# Ethernet_Sheet.net
KiCad netlist of a schematic drawn in Altium Designer
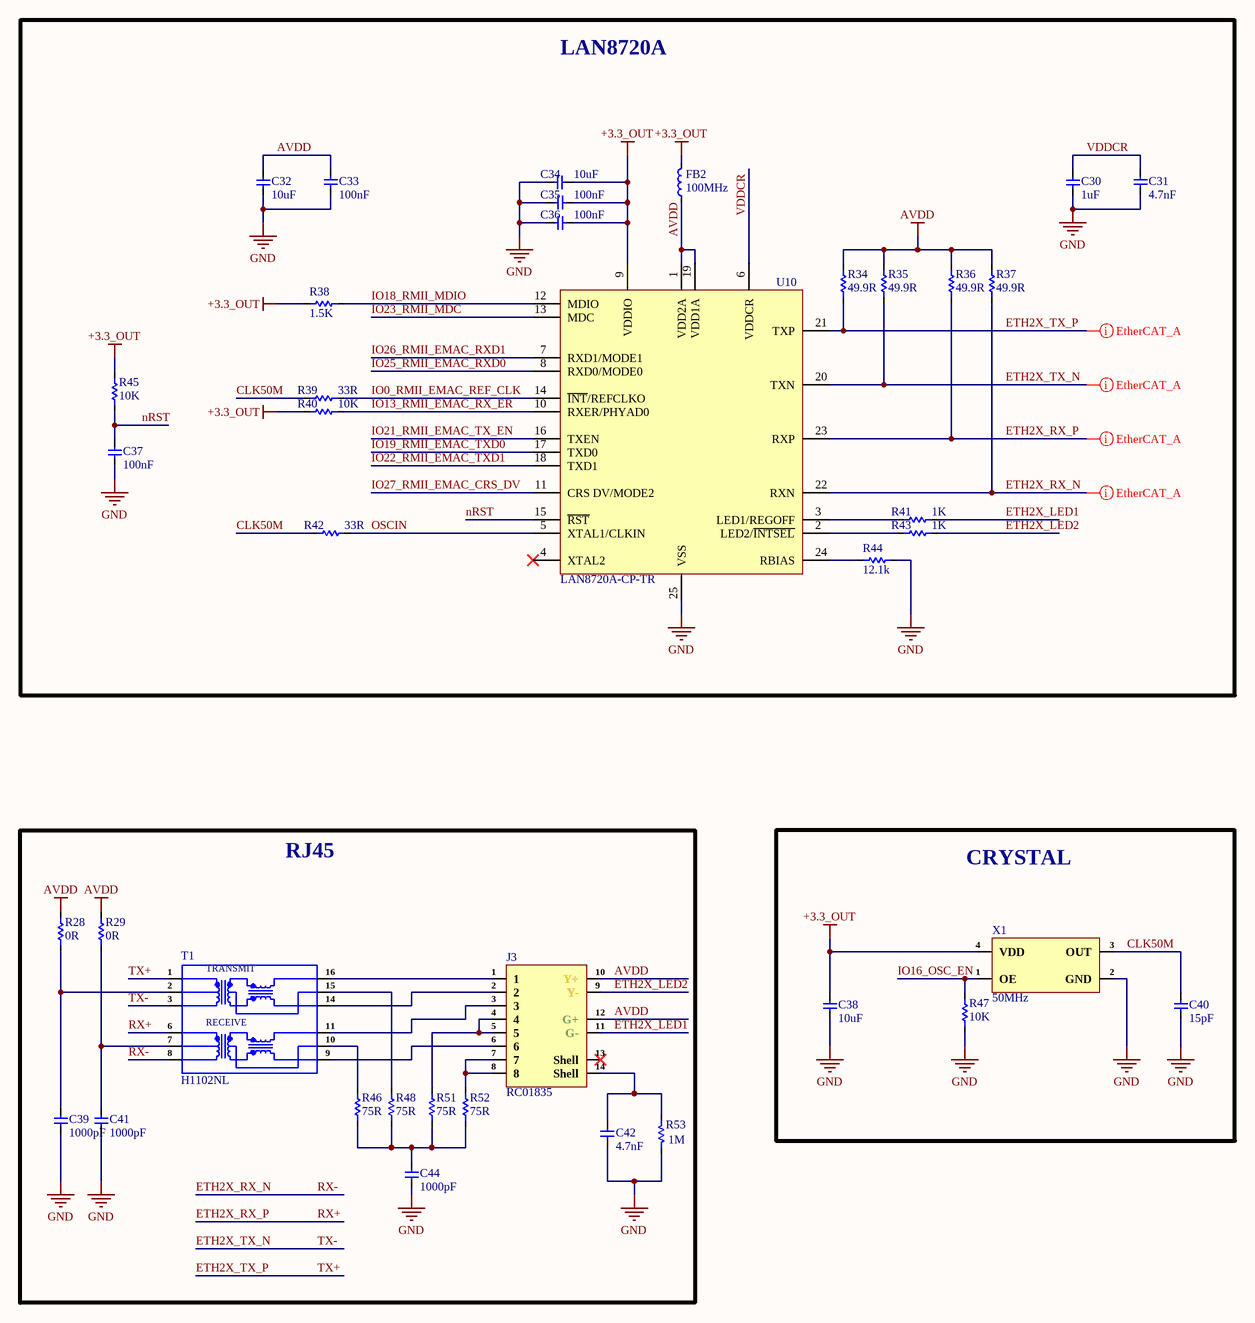
[diagram p0: Ethernet_Sheet.SchDoc]

(export (version "E")
  (design (tool "Eeschema 10.0.6"))
  (components
    (comp (ref "C30")
      (value "1uF")
      (footprint "Cap-0402")
      (description "CAP CER 1UF 16V X5R 0402")
      (fields
        (field (name "MANUFACTURER") "Yageo")
        (field (name "MANUFACTURER PART NUMBER") "CC0402KRX5R7BB105")
      )
      (libsource (lib "eSpark Libraries") (part "CC0402KRX5R7BB105"))
    )
    (comp (ref "C31")
      (value "4.7nF")
      (footprint "Cap-0402")
      (description "CAP CER 4700PF 50V X7R 0402")
      (fields
        (field (name "MANUFACTURER") "Yageo")
        (field (name "MANUFACTURER PART NUMBER") "CC0402KRX7R9BB472")
      )
      (libsource (lib "eSpark Libraries") (part "CC0402KRX7R9BB472"))
    )
    (comp (ref "C32")
      (value "10uF")
      (footprint "Cap-0603")
      (description "CAP CER 10UF 25V X5R 0603")
      (fields
        (field (name "MANUFACTURER") "Samsung")
        (field (name "MANUFACTURER PART NUMBER") "CL10A106MA8NRNC")
      )
      (libsource (lib "eSpark Libraries") (part "CL10A106MA8NRNC"))
    )
    (comp (ref "C33")
      (value "100nF")
      (footprint "cap-0402")
      (description "CAP CER 0.1UF 50V X7R 0402")
      (fields
        (field (name "MANUFACTURER") "TDK")
        (field (name "MANUFACTURER PART NUMBER") "C1005X7R1H104KT000F")
      )
      (libsource (lib "eSpark Libraries") (part "C1005X7R1H104KT000F"))
    )
    (comp (ref "C34")
      (value "10uF")
      (footprint "Cap-0603")
      (description "CAP CER 10UF 25V X5R 0603")
      (fields
        (field (name "MANUFACTURER") "Samsung")
        (field (name "MANUFACTURER PART NUMBER") "CL10A106MA8NRNC")
      )
      (libsource (lib "eSpark Libraries") (part "CL10A106MA8NRNC"))
    )
    (comp (ref "C35")
      (value "100nF")
      (footprint "cap-0402")
      (description "CAP CER 0.1UF 50V X7R 0402")
      (fields
        (field (name "MANUFACTURER") "TDK")
        (field (name "MANUFACTURER PART NUMBER") "C1005X7R1H104KT000F")
      )
      (libsource (lib "eSpark Libraries") (part "C1005X7R1H104KT000F"))
    )
    (comp (ref "C36")
      (value "100nF")
      (footprint "cap-0402")
      (description "CAP CER 0.1UF 50V X7R 0402")
      (fields
        (field (name "MANUFACTURER") "TDK")
        (field (name "MANUFACTURER PART NUMBER") "C1005X7R1H104KT000F")
      )
      (libsource (lib "eSpark Libraries") (part "C1005X7R1H104KT000F"))
    )
    (comp (ref "C37")
      (value "100nF")
      (footprint "cap-0402")
      (description "CAP CER 0.1UF 50V X7R 0402")
      (fields
        (field (name "MANUFACTURER") "TDK")
        (field (name "MANUFACTURER PART NUMBER") "C1005X7R1H104KT000F")
      )
      (libsource (lib "eSpark Libraries") (part "C1005X7R1H104KT000F"))
    )
    (comp (ref "C38")
      (value "10uF")
      (footprint "Cap-0603")
      (description "CAP CER 10UF 25V X5R 0603")
      (fields
        (field (name "MANUFACTURER") "Samsung")
        (field (name "MANUFACTURER PART NUMBER") "CL10A106MA8NRNC")
      )
      (libsource (lib "eSpark Libraries") (part "CL10A106MA8NRNC"))
    )
    (comp (ref "C39")
      (value "1000pF")
      (footprint "Cap-1206")
      (description "CAP CER 1000PF 2KV X7R 1206")
      (fields
        (field (name "MANUFACTURER") "Yageo")
        (field (name "MANUFACTURER PART NUMBER") "CC1206KKX7RDBB102")
      )
      (libsource (lib "eSpark Libraries") (part "CC1206KKX7RDBB102"))
    )
    (comp (ref "C40")
      (value "15pF")
      (footprint "Cap-0603")
      (description "CAP CER 15PF 50V C0G/NPO 0603")
      (fields
        (field (name "MANUFACTURER") "Yageo")
        (field (name "MANUFACTURER PART NUMBER") "CC0603JRNPO9BN150")
      )
      (libsource (lib "eSpark Libraries") (part "CC0603JRNPO9BN150"))
    )
    (comp (ref "C41")
      (value "1000pF")
      (footprint "Cap-1206")
      (description "CAP CER 1000PF 2KV X7R 1206")
      (fields
        (field (name "MANUFACTURER") "Yageo")
        (field (name "MANUFACTURER PART NUMBER") "CC1206KKX7RDBB102")
      )
      (libsource (lib "eSpark Libraries") (part "CC1206KKX7RDBB102"))
    )
    (comp (ref "C42")
      (value "4.7nF")
      (footprint "Cap-0402")
      (description "CAP CER 4700PF 50V X7R 0402")
      (fields
        (field (name "MANUFACTURER") "Yageo")
        (field (name "MANUFACTURER PART NUMBER") "CC0402KRX7R9BB472")
      )
      (libsource (lib "eSpark Libraries") (part "CC0402KRX7R9BB472"))
    )
    (comp (ref "C44")
      (value "1000pF")
      (footprint "Cap-1206")
      (description "CAP CER 1000PF 2KV X7R 1206")
      (fields
        (field (name "MANUFACTURER") "Yageo")
        (field (name "MANUFACTURER PART NUMBER") "CC1206KKX7RDBB102")
      )
      (libsource (lib "eSpark Libraries") (part "CC1206KKX7RDBB102"))
    )
    (comp (ref "FB2")
      (value "100MHz")
      (footprint "IND-1206")
      (description "FERRITE BEAD 120 OHM 1206 1LN")
      (fields
        (field (name "MANUFACTURER") "Murata")
        (field (name "MANUFACTURER PART NUMBER") "BLM31PG121SN1L")
      )
      (libsource (lib "eSpark Libraries") (part "BLM31PG121SN1L"))
    )
    (comp (ref "J3")
      (value "RC01835")
      (footprint "RC01835")
      (fields (field (name "MANUFACTURER") "RCH") (field (name "LCSC PART NUMBER") "C708648"))
      (libsource (lib "eSpark Libraries") (part "RC01835"))
    )
    (comp (ref "R28")
      (value "0R")
      (footprint "Res-0402")
      (description "RES 0 OHM JUMPER 1/16W 0402")
      (fields
        (field (name "MANUFACTURER") "Yageo")
        (field (name "MANUFACTURER PART NUMBER") "RC0402FR-070RL")
      )
      (libsource (lib "eSpark Libraries") (part "RC0402FR-070RL"))
    )
    (comp (ref "R29")
      (value "0R")
      (footprint "Res-0402")
      (description "RES 0 OHM JUMPER 1/16W 0402")
      (fields
        (field (name "MANUFACTURER") "Yageo")
        (field (name "MANUFACTURER PART NUMBER") "RC0402FR-070RL")
      )
      (libsource (lib "eSpark Libraries") (part "RC0402FR-070RL"))
    )
    (comp (ref "R34")
      (value "49.9R")
      (footprint "Res-0603")
      (description "RES 49.9 OHM 1% 1/10W 0603")
      (fields
        (field (name "MANUFACTURER") "Yageo")
        (field (name "MANUFACTURER PART NUMBER") "RC0603FR-0749R9L")
      )
      (libsource (lib "eSpark Libraries") (part "RC0603FR-0749R9L"))
    )
    (comp (ref "R35")
      (value "49.9R")
      (footprint "Res-0603")
      (description "RES 49.9 OHM 1% 1/10W 0603")
      (fields
        (field (name "MANUFACTURER") "Yageo")
        (field (name "MANUFACTURER PART NUMBER") "RC0603FR-0749R9L")
      )
      (libsource (lib "eSpark Libraries") (part "RC0603FR-0749R9L"))
    )
    (comp (ref "R36")
      (value "49.9R")
      (footprint "Res-0603")
      (description "RES 49.9 OHM 1% 1/10W 0603")
      (fields
        (field (name "MANUFACTURER") "Yageo")
        (field (name "MANUFACTURER PART NUMBER") "RC0603FR-0749R9L")
      )
      (libsource (lib "eSpark Libraries") (part "RC0603FR-0749R9L"))
    )
    (comp (ref "R37")
      (value "49.9R")
      (footprint "Res-0603")
      (description "RES 49.9 OHM 1% 1/10W 0603")
      (fields
        (field (name "MANUFACTURER") "Yageo")
        (field (name "MANUFACTURER PART NUMBER") "RC0603FR-0749R9L")
      )
      (libsource (lib "eSpark Libraries") (part "RC0603FR-0749R9L"))
    )
    (comp (ref "R38")
      (value "1.5K")
      (footprint "Res-0402")
      (description "RES 1.5K OHM 1% 1/16W 0402")
      (fields
        (field (name "MANUFACTURER") "Yageo")
        (field (name "MANUFACTURER PART NUMBER") "RC0402FR-071K5L")
      )
      (libsource (lib "eSpark Libraries") (part "RC0402FR-071K5L"))
    )
    (comp (ref "R39")
      (value "33R")
      (footprint "Res-0402")
      (description "RES 33 OHM 1% 1/16W 0402")
      (fields
        (field (name "MANUFACTURER") "Yageo")
        (field (name "MANUFACTURER PART NUMBER") "RC0402FR-0733RL")
      )
      (libsource (lib "eSpark Libraries") (part "RC0402FR-0733RL"))
    )
    (comp (ref "R40")
      (value "10K")
      (footprint "Res-0402")
      (description "RES 10K OHM 1% 1/16W 0402")
      (fields
        (field (name "MANUFACTURER") "Yageo")
        (field (name "MANUFACTURER PART NUMBER") "RC0402FR-0710KL")
      )
      (libsource (lib "eSpark Libraries") (part "RC0402FR-0710KL"))
    )
    (comp (ref "R41")
      (value "1K")
      (footprint "Res-0402")
      (description "RES SMD 1K OHM 1% 1/5W 0402")
      (fields
        (field (name "MANUFACTURER") "Vishay Dale")
        (field (name "MANUFACTURER PART NUMBER") "CRCW04021K00FKEDHP")
      )
      (libsource (lib "eSpark Libraries") (part "CRCW04021K00FKEDHP"))
    )
    (comp (ref "R42")
      (value "33R")
      (footprint "Res-0402")
      (description "RES 33 OHM 1% 1/16W 0402")
      (fields
        (field (name "MANUFACTURER") "Yageo")
        (field (name "MANUFACTURER PART NUMBER") "RC0402FR-0733RL")
      )
      (libsource (lib "eSpark Libraries") (part "RC0402FR-0733RL"))
    )
    (comp (ref "R43")
      (value "1K")
      (footprint "Res-0402")
      (description "RES SMD 1K OHM 1% 1/5W 0402")
      (fields
        (field (name "MANUFACTURER") "Vishay Dale")
        (field (name "MANUFACTURER PART NUMBER") "CRCW04021K00FKEDHP")
      )
      (libsource (lib "eSpark Libraries") (part "CRCW04021K00FKEDHP"))
    )
    (comp (ref "R44")
      (value "12.1k")
      (footprint "Res-0402")
      (description "RES SMD 12.1KOHM 0.1% 1/16W 0402")
      (fields
        (field (name "MANUFACTURER") "Yageo")
        (field (name "MANUFACTURER PART NUMBER") "RT0402BRD0712K1L")
      )
      (libsource (lib "eSpark Libraries") (part "RT0402BRD0712K1L"))
    )
    (comp (ref "R45")
      (value "10K")
      (footprint "Res-0402")
      (description "RES 10K OHM 1% 1/16W 0402")
      (fields
        (field (name "MANUFACTURER") "Yageo")
        (field (name "MANUFACTURER PART NUMBER") "RC0402FR-0710KL")
      )
      (libsource (lib "eSpark Libraries") (part "RC0402FR-0710KL"))
    )
    (comp (ref "R46")
      (value "75R")
      (footprint "Res-0402")
      (description "RES 75 OHM 5% 1/16W 0402")
      (fields
        (field (name "MANUFACTURER") "Yageo")
        (field (name "MANUFACTURER PART NUMBER") "RC0402JR-0775RL")
      )
      (libsource (lib "eSpark Libraries") (part "RC0402JR-0775RL"))
    )
    (comp (ref "R47")
      (value "10K")
      (footprint "Res-0402")
      (description "RES 10K OHM 1% 1/16W 0402")
      (fields
        (field (name "MANUFACTURER") "Yageo")
        (field (name "MANUFACTURER PART NUMBER") "RC0402FR-0710KL")
      )
      (libsource (lib "eSpark Libraries") (part "RC0402FR-0710KL"))
    )
    (comp (ref "R48")
      (value "75R")
      (footprint "Res-0402")
      (description "RES 75 OHM 5% 1/16W 0402")
      (fields
        (field (name "MANUFACTURER") "Yageo")
        (field (name "MANUFACTURER PART NUMBER") "RC0402JR-0775RL")
      )
      (libsource (lib "eSpark Libraries") (part "RC0402JR-0775RL"))
    )
    (comp (ref "R51")
      (value "75R")
      (footprint "Res-0402")
      (description "RES 75 OHM 5% 1/16W 0402")
      (fields
        (field (name "MANUFACTURER") "Yageo")
        (field (name "MANUFACTURER PART NUMBER") "RC0402JR-0775RL")
      )
      (libsource (lib "eSpark Libraries") (part "RC0402JR-0775RL"))
    )
    (comp (ref "R52")
      (value "75R")
      (footprint "Res-0402")
      (description "RES 75 OHM 5% 1/16W 0402")
      (fields
        (field (name "MANUFACTURER") "Yageo")
        (field (name "MANUFACTURER PART NUMBER") "RC0402JR-0775RL")
      )
      (libsource (lib "eSpark Libraries") (part "RC0402JR-0775RL"))
    )
    (comp (ref "R53")
      (value "1M")
      (footprint "Res-0402")
      (description "RES SMD 1M OHM 5% 1/16W 0402")
      (fields
        (field (name "MANUFACTURER") "Yageo")
        (field (name "MANUFACTURER PART NUMBER") "AF0402JR-071ML")
      )
      (libsource (lib "eSpark Libraries") (part "AF0402JR-071ML"))
    )
    (comp (ref "T1")
      (value "H1102NL")
      (footprint "H1102NLT")
      (description "XFRMR MAGNETIC 1PORT 1:1 10/100")
      (fields (field (name "MANUFACTURER") "Pulse") (field (name "LCSC PART NUMBER") "C18584"))
      (libsource (lib "eSpark Libraries") (part "H1102NL"))
    )
    (comp (ref "U10")
      (value "LAN8720A-CP-TR")
      (footprint "LAN8720A-CP-TR")
      (description "IC TRANSCEIVER FULL 2/2 24SQFN")
      (fields (field (name "MANUFACTURER") "MICROCHIP") (field (name "LCSC PART NUMBER") "C45223"))
      (libsource (lib "eSpark Libraries") (part "LAN8720A-CP-TR"))
    )
    (comp (ref "X1")
      (value "50MHz")
      (footprint "OT2EL4C4JI-111OLP-50M")
      (description "1.8V~3.3V ±10ppm ±20ppm CMOS 50MHz SMD3225-4P Crystal Oscillators ROHS")
      (fields
        (field (name "MANUFACTURER") "YXC Crystal Oscillators")
        (field (name "MANUFACTURER PART NUMBER") "OT2EL4C4JI-111OLP-50M")
      )
      (libsource (lib "eSpark Libraries") (part "OT2EL4C4JI-111OLP-50M"))
    )
  )
  (nets
    (net (code "1") (name "+3.3_OUT") (class "Default")
      (node (ref "C34") (pin "2") (pinfunction "2_2") (pintype "passive"))
      (node (ref "C35") (pin "1") (pinfunction "1_1") (pintype "passive"))
      (node (ref "C36") (pin "1") (pinfunction "1_1") (pintype "passive"))
      (node (ref "C38") (pin "2") (pinfunction "2_2") (pintype "passive"))
      (node (ref "FB2") (pin "2") (pinfunction "2_2") (pintype "passive"))
      (node (ref "R38") (pin "2") (pinfunction "2_2") (pintype "passive"))
      (node (ref "R40") (pin "2") (pinfunction "2_2") (pintype "passive"))
      (node (ref "R45") (pin "2") (pinfunction "2_2") (pintype "passive"))
      (node (ref "U10") (pin "9") (pinfunction "VDDIO_9") (pintype "passive"))
      (node (ref "X1") (pin "4") (pinfunction "VDD_4") (pintype "passive"))
    )
    (net (code "2") (name "/CLK50M") (class "Default")
      (node (ref "C40") (pin "2") (pinfunction "2_2") (pintype "passive"))
      (node (ref "R39") (pin "1") (pinfunction "1_1") (pintype "passive"))
      (node (ref "R42") (pin "1") (pinfunction "1_1") (pintype "passive"))
      (node (ref "X1") (pin "3") (pinfunction "OUT_3") (pintype "passive"))
    )
    (net (code "3") (name "/ETH2X_LED1") (class "Default")
      (node (ref "J3") (pin "11") (pinfunction "G-_11") (pintype "passive"))
      (node (ref "R41") (pin "2") (pinfunction "2_2") (pintype "passive"))
    )
    (net (code "4") (name "/ETH2X_LED2") (class "Default")
      (node (ref "J3") (pin "9") (pinfunction "Y-_9") (pintype "passive"))
      (node (ref "R43") (pin "2") (pinfunction "2_2") (pintype "passive"))
    )
    (net (code "5") (name "/ETH2X_RX_N") (class "Default")
      (node (ref "R37") (pin "1") (pinfunction "1_1") (pintype "passive"))
      (node (ref "T1") (pin "8") (pinfunction "8_8") (pintype "passive"))
      (node (ref "U10") (pin "22") (pinfunction "RXN_22") (pintype "passive"))
    )
    (net (code "6") (name "/ETH2X_RX_P") (class "Default")
      (node (ref "R36") (pin "1") (pinfunction "1_1") (pintype "passive"))
      (node (ref "T1") (pin "6") (pinfunction "6_6") (pintype "passive"))
      (node (ref "U10") (pin "23") (pinfunction "RXP_23") (pintype "passive"))
    )
    (net (code "7") (name "/ETH2X_TX_N") (class "Default")
      (node (ref "R35") (pin "1") (pinfunction "1_1") (pintype "passive"))
      (node (ref "T1") (pin "3") (pinfunction "3_3") (pintype "passive"))
      (node (ref "U10") (pin "20") (pinfunction "TXN_20") (pintype "passive"))
    )
    (net (code "8") (name "/ETH2X_TX_P") (class "Default")
      (node (ref "R34") (pin "1") (pinfunction "1_1") (pintype "passive"))
      (node (ref "T1") (pin "1") (pinfunction "1_1") (pintype "passive"))
      (node (ref "U10") (pin "21") (pinfunction "TXP_21") (pintype "passive"))
    )
    (net (code "9") (name "/IO0_RMII_EMAC_REF_CLK") (class "Default")
      (node (ref "R39") (pin "2") (pinfunction "2_2") (pintype "passive"))
      (node (ref "U10") (pin "14") (pinfunction "~{INT}/REFCLKO_14") (pintype "passive"))
    )
    (net (code "10") (name "/IO13_RMII_EMAC_RX_ER") (class "Default")
      (node (ref "R40") (pin "1") (pinfunction "1_1") (pintype "passive"))
      (node (ref "U10") (pin "10") (pinfunction "RXER/PHYAD0_10") (pintype "passive"))
    )
    (net (code "11") (name "/IO16_OSC_EN") (class "Default")
      (node (ref "R47") (pin "1") (pinfunction "1_1") (pintype "passive"))
      (node (ref "X1") (pin "1") (pinfunction "OE_1") (pintype "passive"))
    )
    (net (code "12") (name "/IO18_RMII_MDIO") (class "Default")
      (node (ref "R38") (pin "1") (pinfunction "1_1") (pintype "passive"))
      (node (ref "U10") (pin "12") (pinfunction "MDIO_12") (pintype "passive"))
    )
    (net (code "13") (name "/IO19_RMII_EMAC_TXD0") (class "Default")
      (node (ref "U10") (pin "17") (pinfunction "TXD0_17") (pintype "passive"))
    )
    (net (code "14") (name "/IO21_RMII_EMAC_TX_EN") (class "Default")
      (node (ref "U10") (pin "16") (pinfunction "TXEN_16") (pintype "passive"))
    )
    (net (code "15") (name "/IO22_RMII_EMAC_TXD1") (class "Default")
      (node (ref "U10") (pin "18") (pinfunction "TXD1_18") (pintype "passive"))
    )
    (net (code "16") (name "/IO23_RMII_MDC") (class "Default")
      (node (ref "U10") (pin "13") (pinfunction "MDC_13") (pintype "passive"))
    )
    (net (code "17") (name "/IO25_RMII_EMAC_RXD0") (class "Default")
      (node (ref "U10") (pin "8") (pinfunction "RXD0/MODE0_8") (pintype "passive"))
    )
    (net (code "18") (name "/IO26_RMII_EMAC_RXD1") (class "Default")
      (node (ref "U10") (pin "7") (pinfunction "RXD1/MODE1_7") (pintype "passive"))
    )
    (net (code "19") (name "/IO27_RMII_EMAC_CRS_DV") (class "Default")
      (node (ref "U10") (pin "11") (pinfunction "CRS_DV/MODE2_11") (pintype "passive"))
    )
    (net (code "20") (name "/OSCIN") (class "Default")
      (node (ref "R42") (pin "2") (pinfunction "2_2") (pintype "passive"))
      (node (ref "U10") (pin "5") (pinfunction "XTAL1/CLKIN_5") (pintype "passive"))
    )
    (net (code "21") (name "/VDDCR") (class "Default")
      (node (ref "C30") (pin "2") (pinfunction "2_2") (pintype "passive"))
      (node (ref "C31") (pin "1") (pinfunction "1_1") (pintype "passive"))
      (node (ref "U10") (pin "6") (pinfunction "VDDCR_6") (pintype "passive"))
    )
    (net (code "22") (name "/nRST") (class "Default")
      (node (ref "C37") (pin "2") (pinfunction "2_2") (pintype "passive"))
      (node (ref "R45") (pin "1") (pinfunction "1_1") (pintype "passive"))
      (node (ref "U10") (pin "15") (pinfunction "~{RST}_15") (pintype "passive"))
    )
    (net (code "23") (name "AVDD") (class "Default")
      (node (ref "C32") (pin "2") (pinfunction "2_2") (pintype "passive"))
      (node (ref "C33") (pin "1") (pinfunction "1_1") (pintype "passive"))
      (node (ref "FB2") (pin "1") (pinfunction "1_1") (pintype "passive"))
      (node (ref "J3") (pin "10") (pinfunction "Y+_10") (pintype "passive"))
      (node (ref "J3") (pin "12") (pinfunction "G+_12") (pintype "passive"))
      (node (ref "R28") (pin "2") (pinfunction "2_2") (pintype "passive"))
      (node (ref "R29") (pin "2") (pinfunction "2_2") (pintype "passive"))
      (node (ref "R34") (pin "2") (pinfunction "2_2") (pintype "passive"))
      (node (ref "R35") (pin "2") (pinfunction "2_2") (pintype "passive"))
      (node (ref "R36") (pin "2") (pinfunction "2_2") (pintype "passive"))
      (node (ref "R37") (pin "2") (pinfunction "2_2") (pintype "passive"))
      (node (ref "U10") (pin "1") (pinfunction "VDD2A_1") (pintype "passive"))
      (node (ref "U10") (pin "19") (pinfunction "VDD1A_19") (pintype "passive"))
    )
    (net (code "24") (name "GND") (class "Default")
      (node (ref "C30") (pin "1") (pinfunction "1_1") (pintype "passive"))
      (node (ref "C31") (pin "2") (pinfunction "2_2") (pintype "passive"))
      (node (ref "C32") (pin "1") (pinfunction "1_1") (pintype "passive"))
      (node (ref "C33") (pin "2") (pinfunction "2_2") (pintype "passive"))
      (node (ref "C34") (pin "1") (pinfunction "1_1") (pintype "passive"))
      (node (ref "C35") (pin "2") (pinfunction "2_2") (pintype "passive"))
      (node (ref "C36") (pin "2") (pinfunction "2_2") (pintype "passive"))
      (node (ref "C37") (pin "1") (pinfunction "1_1") (pintype "passive"))
      (node (ref "C38") (pin "1") (pinfunction "1_1") (pintype "passive"))
      (node (ref "C39") (pin "1") (pinfunction "1_1") (pintype "passive"))
      (node (ref "C40") (pin "1") (pinfunction "1_1") (pintype "passive"))
      (node (ref "C41") (pin "1") (pinfunction "1_1") (pintype "passive"))
      (node (ref "C42") (pin "2") (pinfunction "2_2") (pintype "passive"))
      (node (ref "C44") (pin "1") (pinfunction "1_1") (pintype "passive"))
      (node (ref "R44") (pin "1") (pinfunction "1_1") (pintype "passive"))
      (node (ref "R47") (pin "2") (pinfunction "2_2") (pintype "passive"))
      (node (ref "R53") (pin "2") (pinfunction "2_2") (pintype "passive"))
      (node (ref "U10") (pin "25") (pinfunction "VSS_25") (pintype "passive"))
      (node (ref "X1") (pin "2") (pinfunction "GND_2") (pintype "passive"))
    )
    (net (code "25") (name "Net-(C39-Pad2)") (class "Default")
      (node (ref "C39") (pin "2") (pinfunction "2_2") (pintype "passive"))
      (node (ref "R28") (pin "1") (pinfunction "1_1") (pintype "passive"))
      (node (ref "T1") (pin "2") (pinfunction "2_2") (pintype "passive"))
    )
    (net (code "26") (name "Net-(C41-Pad2)") (class "Default")
      (node (ref "C41") (pin "2") (pinfunction "2_2") (pintype "passive"))
      (node (ref "R29") (pin "1") (pinfunction "1_1") (pintype "passive"))
      (node (ref "T1") (pin "7") (pinfunction "7_7") (pintype "passive"))
    )
    (net (code "27") (name "Net-(C42-Pad1)") (class "Default")
      (node (ref "C42") (pin "1") (pinfunction "1_1") (pintype "passive"))
      (node (ref "J3") (pin "14") (pinfunction "Shell_14") (pintype "passive"))
      (node (ref "R53") (pin "1") (pinfunction "1_1") (pintype "passive"))
    )
    (net (code "28") (name "Net-(C44-Pad2)") (class "Default")
      (node (ref "C44") (pin "2") (pinfunction "2_2") (pintype "passive"))
      (node (ref "R46") (pin "1") (pinfunction "1_1") (pintype "passive"))
      (node (ref "R48") (pin "1") (pinfunction "1_1") (pintype "passive"))
      (node (ref "R51") (pin "1") (pinfunction "1_1") (pintype "passive"))
      (node (ref "R52") (pin "1") (pinfunction "1_1") (pintype "passive"))
    )
    (net (code "29") (name "Net-(J3-Pad1)") (class "Default")
      (node (ref "J3") (pin "1") (pinfunction "1_1") (pintype "passive"))
      (node (ref "T1") (pin "16") (pinfunction "16_16") (pintype "passive"))
    )
    (net (code "30") (name "Net-(J3-Pad2)") (class "Default")
      (node (ref "J3") (pin "2") (pinfunction "2_2") (pintype "passive"))
      (node (ref "T1") (pin "14") (pinfunction "14_14") (pintype "passive"))
    )
    (net (code "31") (name "Net-(J3-Pad3)") (class "Default")
      (node (ref "J3") (pin "3") (pinfunction "3_3") (pintype "passive"))
      (node (ref "T1") (pin "11") (pinfunction "11_11") (pintype "passive"))
    )
    (net (code "32") (name "Net-(J3-Pad4)") (class "Default")
      (node (ref "J3") (pin "4") (pinfunction "4_4") (pintype "passive"))
      (node (ref "J3") (pin "5") (pinfunction "5_5") (pintype "passive"))
      (node (ref "R51") (pin "2") (pinfunction "2_2") (pintype "passive"))
    )
    (net (code "33") (name "Net-(J3-Pad6)") (class "Default")
      (node (ref "J3") (pin "6") (pinfunction "6_6") (pintype "passive"))
      (node (ref "T1") (pin "9") (pinfunction "9_9") (pintype "passive"))
    )
    (net (code "34") (name "Net-(J3-Pad7)") (class "Default")
      (node (ref "J3") (pin "7") (pinfunction "7_7") (pintype "passive"))
      (node (ref "J3") (pin "8") (pinfunction "8_8") (pintype "passive"))
      (node (ref "R52") (pin "2") (pinfunction "2_2") (pintype "passive"))
    )
    (net (code "35") (name "Net-(R46-Pad2)") (class "Default")
      (node (ref "R46") (pin "2") (pinfunction "2_2") (pintype "passive"))
      (node (ref "T1") (pin "10") (pinfunction "10_10") (pintype "passive"))
    )
    (net (code "36") (name "Net-(R48-Pad2)") (class "Default")
      (node (ref "R48") (pin "2") (pinfunction "2_2") (pintype "passive"))
      (node (ref "T1") (pin "15") (pinfunction "15_15") (pintype "passive"))
    )
    (net (code "37") (name "Net-(U10-LED1{slash}REGOFF)") (class "Default")
      (node (ref "R41") (pin "1") (pinfunction "1_1") (pintype "passive"))
      (node (ref "U10") (pin "3") (pinfunction "LED1/REGOFF_3") (pintype "passive"))
    )
    (net (code "38") (name "Net-(U10-LED2{slash}~{INTSEL})") (class "Default")
      (node (ref "R43") (pin "1") (pinfunction "1_1") (pintype "passive"))
      (node (ref "U10") (pin "2") (pinfunction "LED2/~{INTSEL}_2") (pintype "passive"))
    )
    (net (code "39") (name "Net-(U10-RBIAS)") (class "Default")
      (node (ref "R44") (pin "2") (pinfunction "2_2") (pintype "passive"))
      (node (ref "U10") (pin "24") (pinfunction "RBIAS_24") (pintype "passive"))
    )
    (net (code "40") (name "unconnected-(J3-Shell-Pad13)") (class "Default")
      (node (ref "J3") (pin "13") (pinfunction "Shell_13") (pintype "passive+no_connect"))
    )
    (net (code "41") (name "unconnected-(U10-XTAL2-Pad4)") (class "Default")
      (node (ref "U10") (pin "4") (pinfunction "XTAL2_4") (pintype "passive+no_connect"))
    )
  )
)
